# Shield.net
KiCad netlist of a schematic drawn in EAGLE
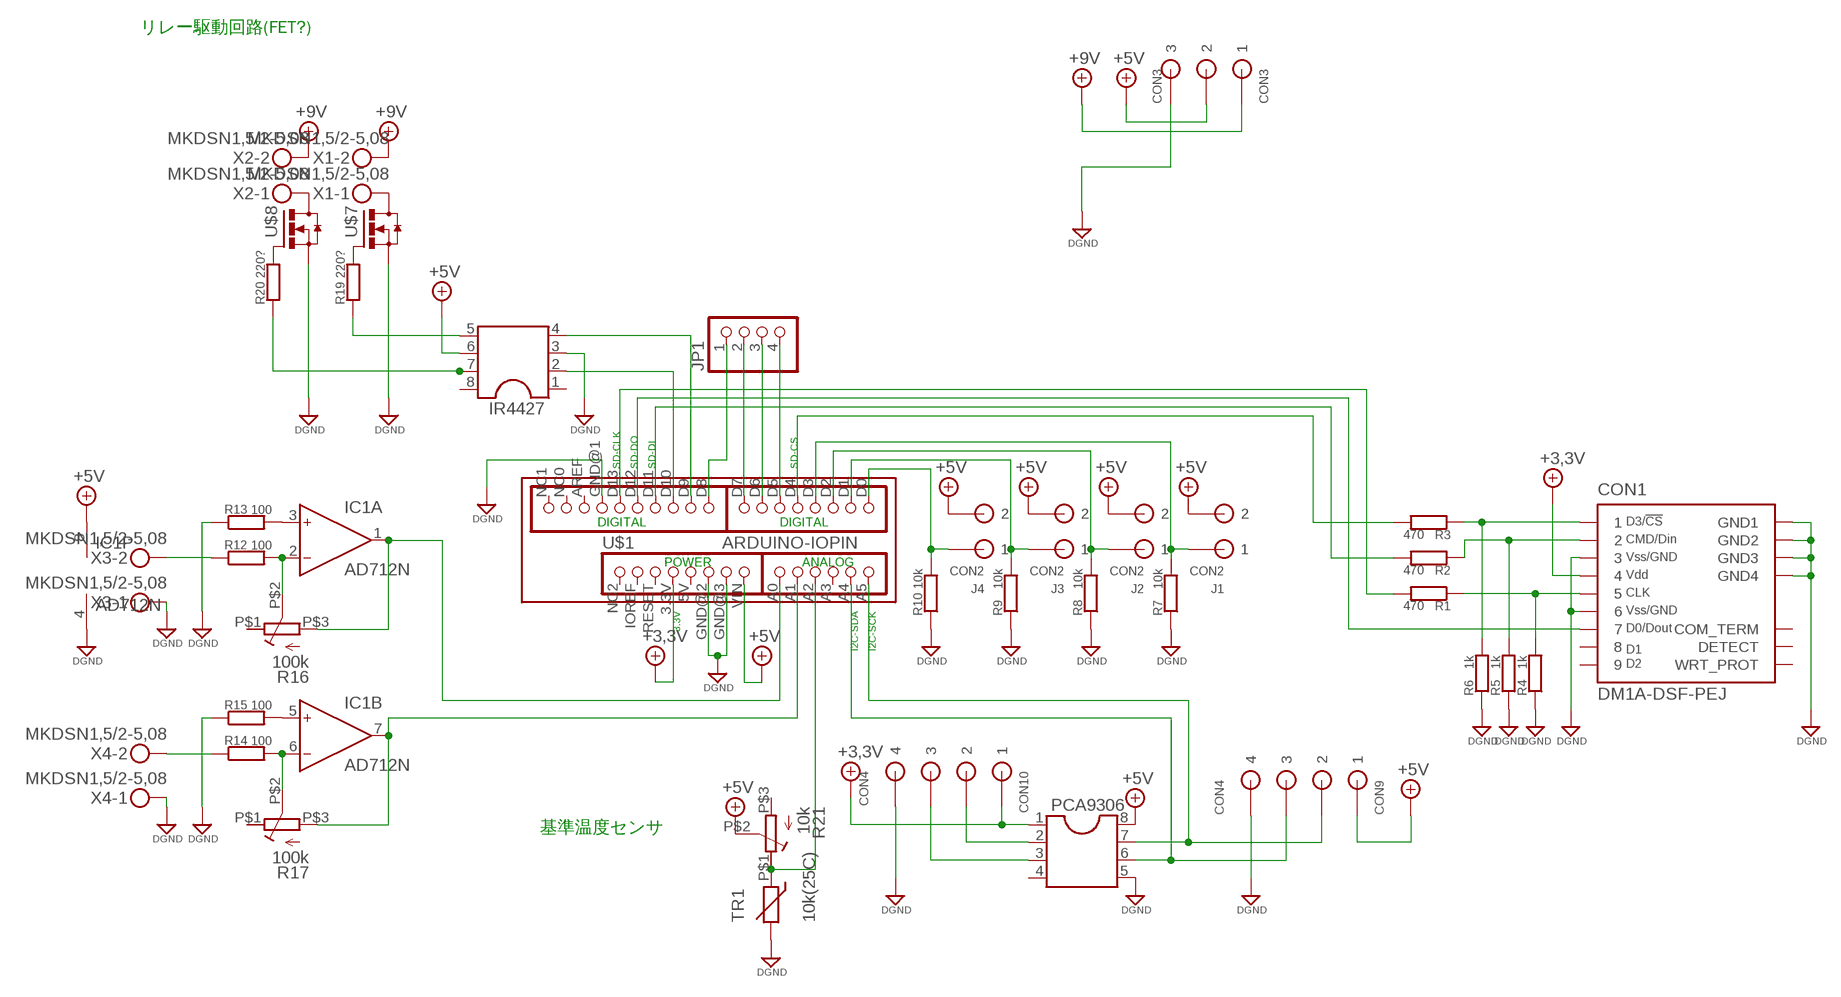
[diagram p0: schematic, sheet 1]

(export (version "E")
  (design (tool "Eeschema 10.0.6"))
  (components
    (comp (ref "CON1")
      (value "DM1A-DSF-PEJ")
      (footprint "eagle-import:DM1A-DSF-PEJ")
      (libsource (lib "eagle-import") (part "DM1A-DSF-PEJ"))
    )
    (comp (ref "CON3")
      (value "CON3")
      (footprint "eagle-import:CON3")
      (libsource (lib "eagle-import") (part "CON3"))
    )
    (comp (ref "CON9")
      (value "CON4")
      (footprint "eagle-import:CON4")
      (libsource (lib "eagle-import") (part "CON4"))
    )
    (comp (ref "CON10")
      (value "CON4")
      (footprint "eagle-import:CON4")
      (libsource (lib "eagle-import") (part "CON4"))
    )
    (comp (ref "IC1")
      (value "AD712N")
      (footprint "eagle-import:DIL08")
      (fields (field (name "MF") "ALTERA CORPORATION") (field (name "MPN") "AD712JNZ"))
      (libsource (lib "eagle-import") (part "AD712N"))
    )
    (comp (ref "IR4427")
      (value "DIL8")
      (footprint "eagle-import:DIL08")
      (libsource (lib "eagle-import") (part "DIL8"))
    )
    (comp (ref "J1")
      (value "CON2")
      (footprint "eagle-import:CON2")
      (libsource (lib "eagle-import") (part "CON2"))
    )
    (comp (ref "J2")
      (value "CON2")
      (footprint "eagle-import:CON2")
      (libsource (lib "eagle-import") (part "CON2"))
    )
    (comp (ref "J3")
      (value "CON2")
      (footprint "eagle-import:CON2")
      (libsource (lib "eagle-import") (part "CON2"))
    )
    (comp (ref "J4")
      (value "CON2")
      (footprint "eagle-import:CON2")
      (libsource (lib "eagle-import") (part "CON2"))
    )
    (comp (ref "JP1")
      (value "PINHD-1X4")
      (footprint "eagle-import:1X04")
      (libsource (lib "eagle-import") (part "PINHD-1X4"))
    )
    (comp (ref "PCA9306")
      (value "DIL8S")
      (footprint "eagle-import:SOCKET-08")
      (libsource (lib "eagle-import") (part "DIL8S"))
    )
    (comp (ref "R1")
      (value "470")
      (footprint "eagle-import:1_4W-H3_(0207_7)")
      (libsource (lib "eagle-import") (part "抵抗0207/7"))
    )
    (comp (ref "R2")
      (value "470")
      (footprint "eagle-import:1_4W-H3_(0207_7)")
      (libsource (lib "eagle-import") (part "抵抗0207/7"))
    )
    (comp (ref "R3")
      (value "470")
      (footprint "eagle-import:1_4W-H3_(0207_7)")
      (libsource (lib "eagle-import") (part "抵抗0207/7"))
    )
    (comp (ref "R4")
      (value "1k")
      (footprint "eagle-import:1_4W-H3_(0207_7)")
      (libsource (lib "eagle-import") (part "抵抗0207/7"))
    )
    (comp (ref "R5")
      (value "1k")
      (footprint "eagle-import:1_4W-H3_(0207_7)")
      (libsource (lib "eagle-import") (part "抵抗0207/7"))
    )
    (comp (ref "R6")
      (value "1k")
      (footprint "eagle-import:1_4W-H3_(0207_7)")
      (libsource (lib "eagle-import") (part "抵抗0207/7"))
    )
    (comp (ref "R7")
      (value "10k")
      (footprint "eagle-import:1_4W-H3_(0207_7)")
      (libsource (lib "eagle-import") (part "抵抗0207/7"))
    )
    (comp (ref "R8")
      (value "10k")
      (footprint "eagle-import:1_4W-H3_(0207_7)")
      (libsource (lib "eagle-import") (part "抵抗0207/7"))
    )
    (comp (ref "R9")
      (value "10k")
      (footprint "eagle-import:1_4W-H3_(0207_7)")
      (libsource (lib "eagle-import") (part "抵抗0207/7"))
    )
    (comp (ref "R10")
      (value "10k")
      (footprint "eagle-import:1_4W-H4_(0207_10)")
      (libsource (lib "eagle-import") (part "抵抗0207/10"))
    )
    (comp (ref "R12")
      (value "100")
      (footprint "eagle-import:1_4W-H3_(0207_7)")
      (libsource (lib "eagle-import") (part "抵抗0207/7"))
    )
    (comp (ref "R13")
      (value "100")
      (footprint "eagle-import:1_4W-H3_(0207_7)")
      (libsource (lib "eagle-import") (part "抵抗0207/7"))
    )
    (comp (ref "R14")
      (value "100")
      (footprint "eagle-import:1_4W-H3_(0207_7)")
      (libsource (lib "eagle-import") (part "抵抗0207/7"))
    )
    (comp (ref "R15")
      (value "100")
      (footprint "eagle-import:1_4W-H3_(0207_7)")
      (libsource (lib "eagle-import") (part "抵抗0207/7"))
    )
    (comp (ref "R16")
      (value "100k")
      (footprint "eagle-import:GF063PB")
      (libsource (lib "eagle-import") (part "抵抗(可変)"))
    )
    (comp (ref "R17")
      (value "100k")
      (footprint "eagle-import:GF063PB")
      (libsource (lib "eagle-import") (part "抵抗(可変)"))
    )
    (comp (ref "R19")
      (value "220?")
      (footprint "eagle-import:1_4W-H3_(0207_7)")
      (libsource (lib "eagle-import") (part "抵抗0207/7"))
    )
    (comp (ref "R20")
      (value "220?")
      (footprint "eagle-import:1_4W-H3_(0207_7)")
      (libsource (lib "eagle-import") (part "抵抗0207/7"))
    )
    (comp (ref "R21")
      (value "10k")
      (footprint "eagle-import:GF063PB")
      (libsource (lib "eagle-import") (part "抵抗(可変)"))
    )
    (comp (ref "TR1")
      (value "10k(25C)")
      (footprint "eagle-import:RS-2,5")
      (libsource (lib "eagle-import") (part "THERMISTOR_R-2,5"))
    )
    (comp (ref "U$1")
      (value "ARDUINO-IOPIN")
      (footprint "eagle-import:ARDUINO-SHIELD-PIN-ONLY")
      (libsource (lib "eagle-import") (part "ARDUINO-IOPIN"))
    )
    (comp (ref "U$7")
      (value "TO-220(MOS-FET_N)")
      (footprint "eagle-import:TO-220")
      (libsource (lib "eagle-import") (part "TO-220(MOS-FET_N)"))
    )
    (comp (ref "U$8")
      (value "TO-220(MOS-FET_N)")
      (footprint "eagle-import:TO-220")
      (libsource (lib "eagle-import") (part "TO-220(MOS-FET_N)"))
    )
    (comp (ref "X1")
      (value "MKDSN1,5/2-5,08")
      (footprint "eagle-import:MKDSN1,5_2-5,08")
      (libsource (lib "eagle-import") (part "MKDSN1,5/2-5,08"))
    )
    (comp (ref "X2")
      (value "MKDSN1,5/2-5,08")
      (footprint "eagle-import:MKDSN1,5_2-5,08")
      (libsource (lib "eagle-import") (part "MKDSN1,5/2-5,08"))
    )
    (comp (ref "X3")
      (value "MKDSN1,5/2-5,08")
      (footprint "eagle-import:MKDSN1,5_2-5,08")
      (libsource (lib "eagle-import") (part "MKDSN1,5/2-5,08"))
    )
    (comp (ref "X4")
      (value "MKDSN1,5/2-5,08")
      (footprint "eagle-import:MKDSN1,5_2-5,08")
      (libsource (lib "eagle-import") (part "MKDSN1,5/2-5,08"))
    )
  )
  (nets
    (net (code "1") (name "+3,3V") (class "Default")
      (node (ref "CON1") (pin "4") (pinfunction "4_4") (pintype "power_in"))
      (node (ref "CON10") (pin "P$1") (pinfunction "1_P$1") (pintype "bidirectional"))
      (node (ref "PCA9306") (pin "1") (pinfunction "1_1") (pintype "passive"))
      (node (ref "U$1") (pin "3.3V") (pinfunction "3,3V_3.3V") (pintype "passive"))
    )
    (net (code "2") (name "+5V") (class "Default")
      (node (ref "CON3") (pin "P$2") (pinfunction "2_P$2") (pintype "bidirectional"))
      (node (ref "CON9") (pin "P$1") (pinfunction "1_P$1") (pintype "bidirectional"))
      (node (ref "IC1") (pin "8") (pinfunction "V+_8") (pintype "power_in"))
      (node (ref "IR4427") (pin "6") (pinfunction "6_6") (pintype "passive"))
      (node (ref "J1") (pin "P$2") (pinfunction "2_P$2") (pintype "bidirectional"))
      (node (ref "J2") (pin "P$2") (pinfunction "2_P$2") (pintype "bidirectional"))
      (node (ref "J3") (pin "P$2") (pinfunction "2_P$2") (pintype "bidirectional"))
      (node (ref "J4") (pin "P$2") (pinfunction "2_P$2") (pintype "bidirectional"))
      (node (ref "PCA9306") (pin "8") (pinfunction "8_8") (pintype "passive"))
      (node (ref "R21") (pin "P$2") (pinfunction "S_P$2") (pintype "passive"))
      (node (ref "U$1") (pin "VIN") (pinfunction "VIN_VIN") (pintype "passive"))
    )
    (net (code "3") (name "+9V") (class "Default")
      (node (ref "CON3") (pin "P$1") (pinfunction "1_P$1") (pintype "bidirectional"))
      (node (ref "X1") (pin "2") (pinfunction "KL_2") (pintype "passive"))
      (node (ref "X2") (pin "2") (pinfunction "KL_2") (pintype "passive"))
    )
    (net (code "4") (name "DGND") (class "Default")
      (node (ref "CON1") (pin "3") (pinfunction "3_3") (pintype "power_in"))
      (node (ref "CON1") (pin "6") (pinfunction "6_6") (pintype "power_in"))
      (node (ref "CON1") (pin "GND1") (pinfunction "GND1_GND1") (pintype "power_in"))
      (node (ref "CON1") (pin "GND2") (pinfunction "GND2_GND2") (pintype "power_in"))
      (node (ref "CON1") (pin "GND3") (pinfunction "GND3_GND3") (pintype "power_in"))
      (node (ref "CON1") (pin "GND4") (pinfunction "GND4_GND4") (pintype "power_in"))
      (node (ref "CON10") (pin "P$4") (pinfunction "4_P$4") (pintype "bidirectional"))
      (node (ref "CON3") (pin "P$3") (pinfunction "3_P$3") (pintype "bidirectional"))
      (node (ref "CON9") (pin "P$4") (pinfunction "4_P$4") (pintype "bidirectional"))
      (node (ref "IC1") (pin "4") (pinfunction "V-_4") (pintype "power_in"))
      (node (ref "IR4427") (pin "3") (pinfunction "3_3") (pintype "passive"))
      (node (ref "PCA9306") (pin "5") (pinfunction "5_5") (pintype "passive"))
      (node (ref "R10") (pin "1") (pinfunction "1_1") (pintype "passive"))
      (node (ref "R13") (pin "1") (pinfunction "1_1") (pintype "passive"))
      (node (ref "R15") (pin "1") (pinfunction "1_1") (pintype "passive"))
      (node (ref "R4") (pin "1") (pinfunction "1_1") (pintype "passive"))
      (node (ref "R5") (pin "1") (pinfunction "1_1") (pintype "passive"))
      (node (ref "R6") (pin "1") (pinfunction "1_1") (pintype "passive"))
      (node (ref "R7") (pin "1") (pinfunction "1_1") (pintype "passive"))
      (node (ref "R8") (pin "1") (pinfunction "1_1") (pintype "passive"))
      (node (ref "R9") (pin "1") (pinfunction "1_1") (pintype "passive"))
      (node (ref "TR1") (pin "2") (pinfunction "2_2") (pintype "passive"))
      (node (ref "U$1") (pin "GND@1") (pinfunction "GND0_GND@1") (pintype "passive"))
      (node (ref "U$1") (pin "GND@2") (pinfunction "GND1_GND@2") (pintype "passive"))
      (node (ref "U$1") (pin "GND@3") (pinfunction "GND2_GND@3") (pintype "passive"))
      (node (ref "U$7") (pin "3") (pinfunction "S_3") (pintype "passive"))
      (node (ref "U$8") (pin "3") (pinfunction "S_3") (pintype "passive"))
      (node (ref "X3") (pin "1") (pinfunction "KL_1") (pintype "passive"))
      (node (ref "X4") (pin "1") (pinfunction "KL_1") (pintype "passive"))
    )
    (net (code "5") (name "Net-(CON1-Pad1)") (class "Default")
      (node (ref "CON1") (pin "1") (pinfunction "1_1") (pintype "bidirectional"))
      (node (ref "R3") (pin "1") (pinfunction "1_1") (pintype "passive"))
      (node (ref "R6") (pin "2") (pinfunction "2_2") (pintype "passive"))
    )
    (net (code "6") (name "Net-(CON1-Pad2)") (class "Default")
      (node (ref "CON1") (pin "2") (pinfunction "2_2") (pintype "input"))
      (node (ref "R2") (pin "1") (pinfunction "1_1") (pintype "passive"))
      (node (ref "R5") (pin "2") (pinfunction "2_2") (pintype "passive"))
    )
    (net (code "7") (name "Net-(CON1-Pad5)") (class "Default")
      (node (ref "CON1") (pin "5") (pinfunction "5_5") (pintype "input"))
      (node (ref "R1") (pin "1") (pinfunction "1_1") (pintype "passive"))
      (node (ref "R4") (pin "2") (pinfunction "2_2") (pintype "passive"))
    )
    (net (code "8") (name "Net-(CON1-Pad7)") (class "Default")
      (node (ref "CON1") (pin "7") (pinfunction "7_7") (pintype "bidirectional"))
      (node (ref "U$1") (pin "D12") (pinfunction "D12_D12") (pintype "passive"))
    )
    (net (code "9") (name "Net-(CON9-2)") (class "Default")
      (node (ref "CON9") (pin "P$2") (pinfunction "2_P$2") (pintype "bidirectional"))
      (node (ref "PCA9306") (pin "7") (pinfunction "7_7") (pintype "passive"))
      (node (ref "U$1") (pin "A5") (pinfunction "A5_A5") (pintype "passive"))
    )
    (net (code "10") (name "Net-(CON9-3)") (class "Default")
      (node (ref "CON9") (pin "P$3") (pinfunction "3_P$3") (pintype "bidirectional"))
      (node (ref "PCA9306") (pin "6") (pinfunction "6_6") (pintype "passive"))
      (node (ref "U$1") (pin "A4") (pinfunction "A4_A4") (pintype "passive"))
    )
    (net (code "11") (name "Net-(CON10-2)") (class "Default")
      (node (ref "CON10") (pin "P$2") (pinfunction "2_P$2") (pintype "bidirectional"))
      (node (ref "PCA9306") (pin "2") (pinfunction "2_2") (pintype "passive"))
    )
    (net (code "12") (name "Net-(CON10-3)") (class "Default")
      (node (ref "CON10") (pin "P$3") (pinfunction "3_P$3") (pintype "bidirectional"))
      (node (ref "PCA9306") (pin "3") (pinfunction "3_3") (pintype "passive"))
    )
    (net (code "13") (name "Net-(IC1A-IN+)") (class "Default")
      (node (ref "IC1") (pin "3") (pinfunction "IN+_3") (pintype "input"))
      (node (ref "R13") (pin "2") (pinfunction "2_2") (pintype "passive"))
    )
    (net (code "14") (name "Net-(IC1A-IN-)") (class "Default")
      (node (ref "IC1") (pin "2") (pinfunction "IN-_2") (pintype "input"))
      (node (ref "R12") (pin "2") (pinfunction "2_2") (pintype "passive"))
      (node (ref "R16") (pin "P$2") (pinfunction "S_P$2") (pintype "passive"))
    )
    (net (code "15") (name "Net-(IC1A-OUT)") (class "Default")
      (node (ref "IC1") (pin "1") (pinfunction "OUT_1") (pintype "output"))
      (node (ref "R16") (pin "P$3") (pinfunction "A_P$3") (pintype "passive"))
      (node (ref "U$1") (pin "A0") (pinfunction "A0_A0") (pintype "passive"))
    )
    (net (code "16") (name "Net-(IC1B-IN+)") (class "Default")
      (node (ref "IC1") (pin "5") (pinfunction "IN+_5") (pintype "input"))
      (node (ref "R15") (pin "2") (pinfunction "2_2") (pintype "passive"))
    )
    (net (code "17") (name "Net-(IC1B-IN-)") (class "Default")
      (node (ref "IC1") (pin "6") (pinfunction "IN-_6") (pintype "input"))
      (node (ref "R14") (pin "2") (pinfunction "2_2") (pintype "passive"))
      (node (ref "R17") (pin "P$2") (pinfunction "S_P$2") (pintype "passive"))
    )
    (net (code "18") (name "Net-(IC1B-OUT)") (class "Default")
      (node (ref "IC1") (pin "7") (pinfunction "OUT_7") (pintype "output"))
      (node (ref "R17") (pin "P$3") (pinfunction "A_P$3") (pintype "passive"))
      (node (ref "U$1") (pin "A1") (pinfunction "A1_A1") (pintype "passive"))
    )
    (net (code "19") (name "Net-(IR4427-Pad2)") (class "Default")
      (node (ref "IR4427") (pin "2") (pinfunction "2_2") (pintype "passive"))
      (node (ref "U$1") (pin "D10") (pinfunction "D10_D10") (pintype "passive"))
    )
    (net (code "20") (name "Net-(IR4427-Pad4)") (class "Default")
      (node (ref "IR4427") (pin "4") (pinfunction "4_4") (pintype "passive"))
      (node (ref "U$1") (pin "D9") (pinfunction "D9_D9") (pintype "passive"))
    )
    (net (code "21") (name "Net-(IR4427-Pad5)") (class "Default")
      (node (ref "IR4427") (pin "5") (pinfunction "5_5") (pintype "passive"))
      (node (ref "R19") (pin "1") (pinfunction "1_1") (pintype "passive"))
    )
    (net (code "22") (name "Net-(IR4427-Pad7)") (class "Default")
      (node (ref "IR4427") (pin "7") (pinfunction "7_7") (pintype "passive"))
      (node (ref "R20") (pin "1") (pinfunction "1_1") (pintype "passive"))
    )
    (net (code "23") (name "Net-(J1-1)") (class "Default")
      (node (ref "J1") (pin "P$1") (pinfunction "1_P$1") (pintype "bidirectional"))
      (node (ref "R7") (pin "2") (pinfunction "2_2") (pintype "passive"))
      (node (ref "U$1") (pin "D3") (pinfunction "D3_D3") (pintype "passive"))
    )
    (net (code "24") (name "Net-(J2-1)") (class "Default")
      (node (ref "J2") (pin "P$1") (pinfunction "1_P$1") (pintype "bidirectional"))
      (node (ref "R8") (pin "2") (pinfunction "2_2") (pintype "passive"))
      (node (ref "U$1") (pin "D2") (pinfunction "D2_D2") (pintype "passive"))
    )
    (net (code "25") (name "Net-(J3-1)") (class "Default")
      (node (ref "J3") (pin "P$1") (pinfunction "1_P$1") (pintype "bidirectional"))
      (node (ref "R9") (pin "2") (pinfunction "2_2") (pintype "passive"))
      (node (ref "U$1") (pin "D1") (pinfunction "D1_D1") (pintype "passive"))
    )
    (net (code "26") (name "Net-(J4-1)") (class "Default")
      (node (ref "J4") (pin "P$1") (pinfunction "1_P$1") (pintype "bidirectional"))
      (node (ref "R10") (pin "2") (pinfunction "2_2") (pintype "passive"))
      (node (ref "U$1") (pin "D0") (pinfunction "D0_D0") (pintype "passive"))
    )
    (net (code "27") (name "Net-(JP1-Pad1)") (class "Default")
      (node (ref "JP1") (pin "1") (pinfunction "1_1") (pintype "passive"))
      (node (ref "U$1") (pin "D8") (pinfunction "D8_D8") (pintype "passive"))
    )
    (net (code "28") (name "Net-(JP1-Pad2)") (class "Default")
      (node (ref "JP1") (pin "2") (pinfunction "2_2") (pintype "passive"))
      (node (ref "U$1") (pin "D7") (pinfunction "D7_D7") (pintype "passive"))
    )
    (net (code "29") (name "Net-(JP1-Pad3)") (class "Default")
      (node (ref "JP1") (pin "3") (pinfunction "3_3") (pintype "passive"))
      (node (ref "U$1") (pin "D6") (pinfunction "D6_D6") (pintype "passive"))
    )
    (net (code "30") (name "Net-(JP1-Pad4)") (class "Default")
      (node (ref "JP1") (pin "4") (pinfunction "4_4") (pintype "passive"))
      (node (ref "U$1") (pin "D5") (pinfunction "D5_D5") (pintype "passive"))
    )
    (net (code "31") (name "Net-(R1-Pad2)") (class "Default")
      (node (ref "R1") (pin "2") (pinfunction "2_2") (pintype "passive"))
      (node (ref "U$1") (pin "D13") (pinfunction "D13_D13") (pintype "passive"))
    )
    (net (code "32") (name "Net-(R2-Pad2)") (class "Default")
      (node (ref "R2") (pin "2") (pinfunction "2_2") (pintype "passive"))
      (node (ref "U$1") (pin "D11") (pinfunction "D11_D11") (pintype "passive"))
    )
    (net (code "33") (name "Net-(R3-Pad2)") (class "Default")
      (node (ref "R3") (pin "2") (pinfunction "2_2") (pintype "passive"))
      (node (ref "U$1") (pin "D4") (pinfunction "D4_D4") (pintype "passive"))
    )
    (net (code "34") (name "Net-(R21-E)") (class "Default")
      (node (ref "R21") (pin "P$1") (pinfunction "E_P$1") (pintype "passive"))
      (node (ref "TR1") (pin "1") (pinfunction "1_1") (pintype "passive"))
      (node (ref "U$1") (pin "A2") (pinfunction "A2_A2") (pintype "passive"))
    )
    (net (code "35") (name "Net-(U$7-D)") (class "Default")
      (node (ref "U$7") (pin "2") (pinfunction "D_2") (pintype "passive"))
      (node (ref "X1") (pin "1") (pinfunction "KL_1") (pintype "passive"))
    )
    (net (code "36") (name "Net-(U$7-G)") (class "Default")
      (node (ref "R19") (pin "2") (pinfunction "2_2") (pintype "passive"))
      (node (ref "U$7") (pin "1") (pinfunction "G_1") (pintype "passive"))
    )
    (net (code "37") (name "Net-(U$8-D)") (class "Default")
      (node (ref "U$8") (pin "2") (pinfunction "D_2") (pintype "passive"))
      (node (ref "X2") (pin "1") (pinfunction "KL_1") (pintype "passive"))
    )
    (net (code "38") (name "Net-(U$8-G)") (class "Default")
      (node (ref "R20") (pin "2") (pinfunction "2_2") (pintype "passive"))
      (node (ref "U$8") (pin "1") (pinfunction "G_1") (pintype "passive"))
    )
    (net (code "39") (name "Net-(X3B-KL)") (class "Default")
      (node (ref "R12") (pin "1") (pinfunction "1_1") (pintype "passive"))
      (node (ref "X3") (pin "2") (pinfunction "KL_2") (pintype "passive"))
    )
    (net (code "40") (name "Net-(X4B-KL)") (class "Default")
      (node (ref "R14") (pin "1") (pinfunction "1_1") (pintype "passive"))
      (node (ref "X4") (pin "2") (pinfunction "KL_2") (pintype "passive"))
    )
    (net (code "41") (name "unconnected-(CON1-Pad8)") (class "Default")
      (node (ref "CON1") (pin "8") (pinfunction "8_8") (pintype "bidirectional"))
    )
    (net (code "42") (name "unconnected-(CON1-Pad9)") (class "Default")
      (node (ref "CON1") (pin "9") (pinfunction "9_9") (pintype "bidirectional"))
    )
    (net (code "43") (name "unconnected-(CON1-PadCOM_TERM)") (class "Default")
      (node (ref "CON1") (pin "COM_TERM") (pinfunction "COM_TERM_COM_TERM") (pintype "output"))
    )
    (net (code "44") (name "unconnected-(CON1-PadDETECT)") (class "Default")
      (node (ref "CON1") (pin "DETECT") (pinfunction "DETECT_DETECT") (pintype "output"))
    )
    (net (code "45") (name "unconnected-(CON1-PadWRT_PROT)") (class "Default")
      (node (ref "CON1") (pin "WRT_PROT") (pinfunction "WRT_PROT_WRT_PROT") (pintype "output"))
    )
    (net (code "46") (name "unconnected-(IR4427-Pad1)") (class "Default")
      (node (ref "IR4427") (pin "1") (pinfunction "1_1") (pintype "passive"))
    )
    (net (code "47") (name "unconnected-(IR4427-Pad8)") (class "Default")
      (node (ref "IR4427") (pin "8") (pinfunction "8_8") (pintype "passive"))
    )
    (net (code "48") (name "unconnected-(PCA9306-Pad4)") (class "Default")
      (node (ref "PCA9306") (pin "4") (pinfunction "4_4") (pintype "passive"))
    )
    (net (code "49") (name "unconnected-(R16-E-PadP$1)") (class "Default")
      (node (ref "R16") (pin "P$1") (pinfunction "E_P$1") (pintype "passive"))
    )
    (net (code "50") (name "unconnected-(R17-E-PadP$1)") (class "Default")
      (node (ref "R17") (pin "P$1") (pinfunction "E_P$1") (pintype "passive"))
    )
    (net (code "51") (name "unconnected-(R21-A-PadP$3)") (class "Default")
      (node (ref "R21") (pin "P$3") (pinfunction "A_P$3") (pintype "passive"))
    )
    (net (code "52") (name "unconnected-(U$1-Pad5V)") (class "Default")
      (node (ref "U$1") (pin "5V") (pinfunction "5V_5V") (pintype "passive"))
    )
    (net (code "53") (name "unconnected-(U$1-PadA3)") (class "Default")
      (node (ref "U$1") (pin "A3") (pinfunction "A3_A3") (pintype "passive"))
    )
    (net (code "54") (name "unconnected-(U$1-PadAREF)") (class "Default")
      (node (ref "U$1") (pin "AREF") (pinfunction "AREF_AREF") (pintype "passive"))
    )
    (net (code "55") (name "unconnected-(U$1-PadIOREF)") (class "Default")
      (node (ref "U$1") (pin "IOREF") (pinfunction "IOREF_IOREF") (pintype "passive"))
    )
    (net (code "56") (name "unconnected-(U$1-PadNC0)") (class "Default")
      (node (ref "U$1") (pin "NC0") (pinfunction "NC0_NC0") (pintype "passive"))
    )
    (net (code "57") (name "unconnected-(U$1-PadNC1)") (class "Default")
      (node (ref "U$1") (pin "NC1") (pinfunction "NC1_NC1") (pintype "passive"))
    )
    (net (code "58") (name "unconnected-(U$1-PadNC2)") (class "Default")
      (node (ref "U$1") (pin "NC2") (pinfunction "NC2_NC2") (pintype "passive"))
    )
    (net (code "59") (name "unconnected-(U$1-PadRESET)") (class "Default")
      (node (ref "U$1") (pin "RESET") (pinfunction "RESET_RESET") (pintype "passive"))
    )
  )
)
